# shift_driver.net
KiCad netlist of a schematic drawn in EAGLE
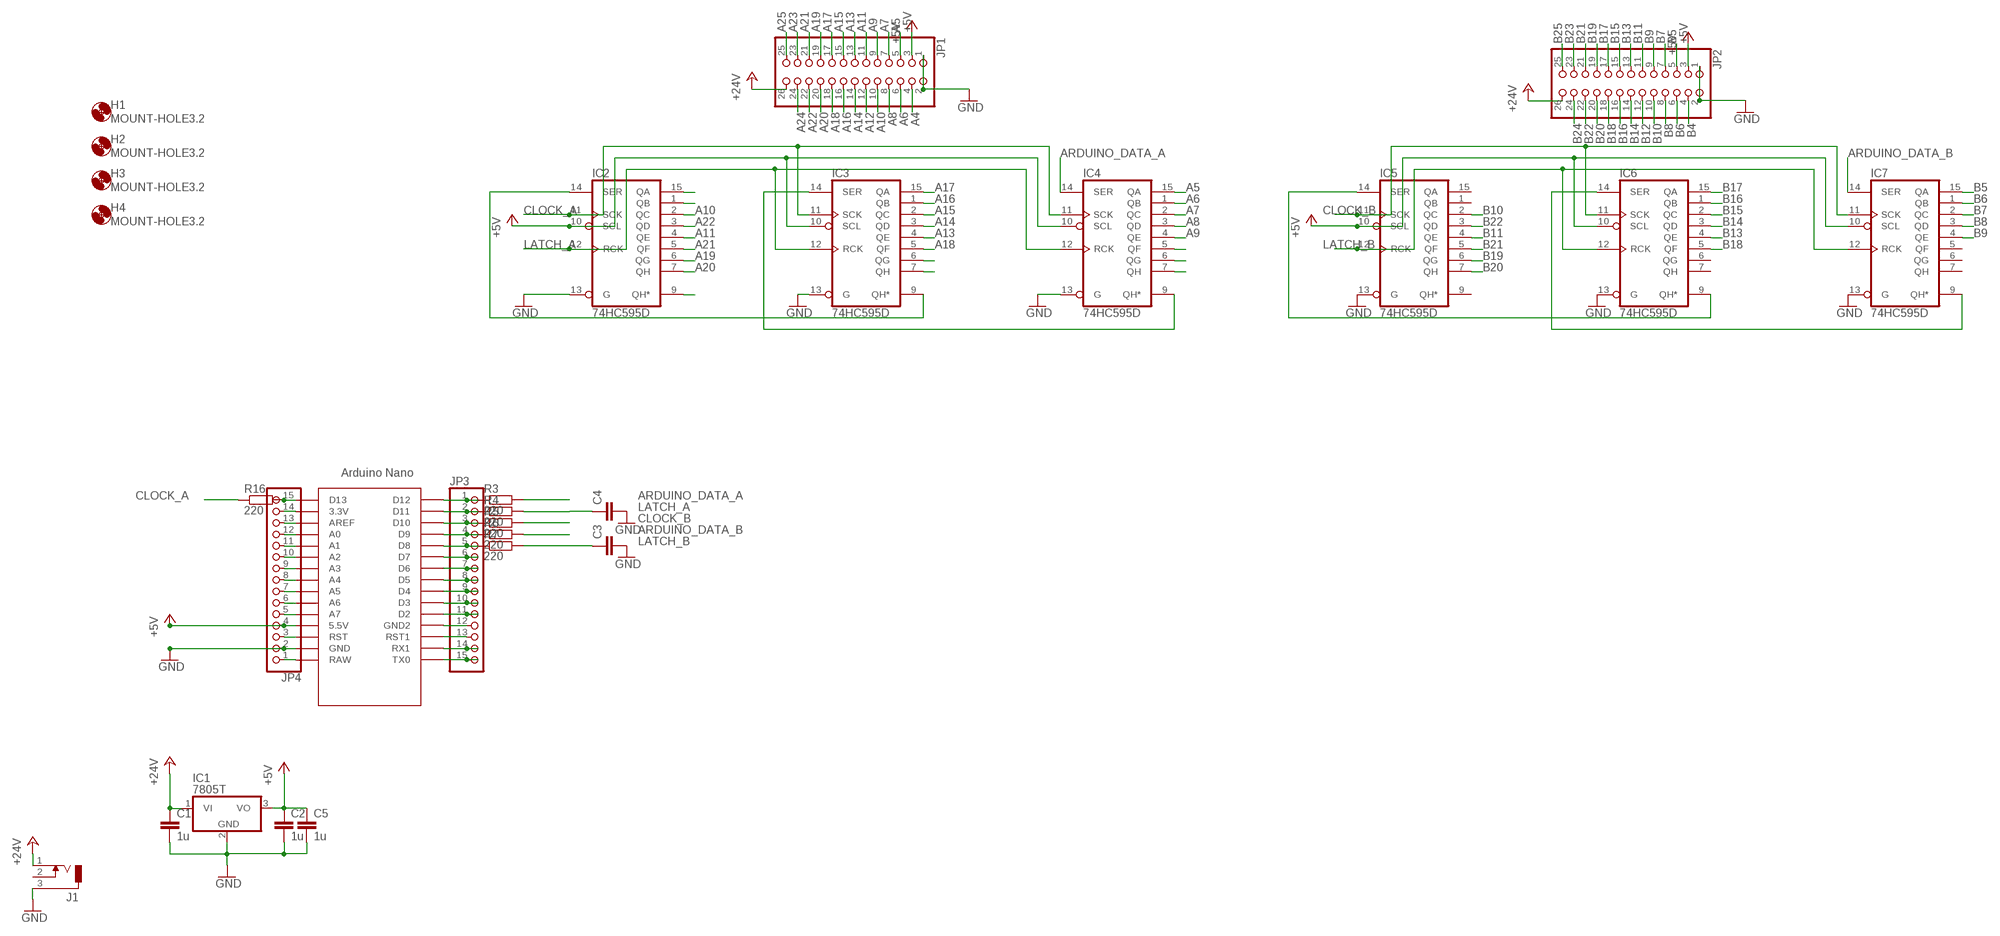
[diagram p0: schematic, sheet 1]

(export (version "E")
  (design (tool "Eeschema 10.0.6"))
  (components
    (comp (ref "C1")
      (value "1u")
      (footprint "eagle-import:C0805")
      (libsource (lib "eagle-import") (part "C-EUC0805"))
    )
    (comp (ref "C2")
      (value "1u")
      (footprint "eagle-import:C0805")
      (libsource (lib "eagle-import") (part "C-EUC0805"))
    )
    (comp (ref "C3")
      (value "C-EUC0805")
      (footprint "eagle-import:C0805")
      (libsource (lib "eagle-import") (part "C-EUC0805"))
    )
    (comp (ref "C4")
      (value "C-EUC0805")
      (footprint "eagle-import:C0805")
      (libsource (lib "eagle-import") (part "C-EUC0805"))
    )
    (comp (ref "C5")
      (value "1u")
      (footprint "eagle-import:C0805")
      (libsource (lib "eagle-import") (part "C-EUC0805"))
    )
    (comp (ref "H1")
      (value "MOUNT-HOLE3.2")
      (footprint "eagle-import:3,2")
      (libsource (lib "eagle-import") (part "MOUNT-HOLE3.2"))
    )
    (comp (ref "H2")
      (value "MOUNT-HOLE3.2")
      (footprint "eagle-import:3,2")
      (libsource (lib "eagle-import") (part "MOUNT-HOLE3.2"))
    )
    (comp (ref "H3")
      (value "MOUNT-HOLE3.2")
      (footprint "eagle-import:3,2")
      (libsource (lib "eagle-import") (part "MOUNT-HOLE3.2"))
    )
    (comp (ref "H4")
      (value "MOUNT-HOLE3.2")
      (footprint "eagle-import:3,2")
      (libsource (lib "eagle-import") (part "MOUNT-HOLE3.2"))
    )
    (comp (ref "IC1")
      (value "7805T")
      (footprint "eagle-import:TO220H")
      (libsource (lib "eagle-import") (part "78T05"))
    )
    (comp (ref "IC2")
      (value "74HC595D")
      (footprint "eagle-import:SO16")
      (libsource (lib "eagle-import") (part "74595DHC"))
    )
    (comp (ref "IC3")
      (value "74HC595D")
      (footprint "eagle-import:SO16")
      (libsource (lib "eagle-import") (part "74595DHC"))
    )
    (comp (ref "IC4")
      (value "74HC595D")
      (footprint "eagle-import:SO16")
      (libsource (lib "eagle-import") (part "74595DHC"))
    )
    (comp (ref "IC5")
      (value "74HC595D")
      (footprint "eagle-import:SO16")
      (libsource (lib "eagle-import") (part "74595DHC"))
    )
    (comp (ref "IC6")
      (value "74HC595D")
      (footprint "eagle-import:SO16")
      (libsource (lib "eagle-import") (part "74595DHC"))
    )
    (comp (ref "IC7")
      (value "74HC595D")
      (footprint "eagle-import:SO16")
      (libsource (lib "eagle-import") (part "74595DHC"))
    )
    (comp (ref "J1")
      (value "DCJ0303")
      (footprint "eagle-import:DCJ0303")
      (libsource (lib "eagle-import") (part "DCJ0303"))
    )
    (comp (ref "JP1")
      (value "PINHD-2X13")
      (footprint "eagle-import:2X13")
      (libsource (lib "eagle-import") (part "PINHD-2X13"))
    )
    (comp (ref "JP2")
      (value "PINHD-2X13")
      (footprint "eagle-import:2X13")
      (libsource (lib "eagle-import") (part "PINHD-2X13"))
    )
    (comp (ref "JP3")
      (value "PINHD-1X15")
      (footprint "eagle-import:1X15")
      (libsource (lib "eagle-import") (part "PINHD-1X15"))
    )
    (comp (ref "JP4")
      (value "PINHD-1X15")
      (footprint "eagle-import:1X15")
      (libsource (lib "eagle-import") (part "PINHD-1X15"))
    )
    (comp (ref "R3")
      (value "220")
      (footprint "eagle-import:R0603")
      (libsource (lib "eagle-import") (part "R-EU_R0603"))
    )
    (comp (ref "R4")
      (value "220")
      (footprint "eagle-import:R0603")
      (libsource (lib "eagle-import") (part "R-EU_R0603"))
    )
    (comp (ref "R5")
      (value "220")
      (footprint "eagle-import:R0603")
      (libsource (lib "eagle-import") (part "R-EU_R0603"))
    )
    (comp (ref "R6")
      (value "220")
      (footprint "eagle-import:R0603")
      (libsource (lib "eagle-import") (part "R-EU_R0603"))
    )
    (comp (ref "R7")
      (value "220")
      (footprint "eagle-import:R0603")
      (libsource (lib "eagle-import") (part "R-EU_R0603"))
    )
    (comp (ref "R16")
      (value "220")
      (footprint "eagle-import:R0603")
      (libsource (lib "eagle-import") (part "R-EU_R0603"))
    )
    (comp (ref "U$1")
      (value "NANO")
      (footprint "eagle-import:NANO")
      (libsource (lib "eagle-import") (part "NANO"))
    )
  )
  (nets
    (net (code "1") (name "+5V") (class "Default")
      (node (ref "C2") (pin "1") (pinfunction "1_1") (pintype "passive"))
      (node (ref "C5") (pin "1") (pinfunction "1_1") (pintype "passive"))
      (node (ref "IC1") (pin "3") (pinfunction "VO_3") (pintype "passive"))
      (node (ref "IC2") (pin "10") (pinfunction "SCL_10") (pintype "input"))
      (node (ref "IC3") (pin "10") (pinfunction "SCL_10") (pintype "input"))
      (node (ref "IC4") (pin "10") (pinfunction "SCL_10") (pintype "input"))
      (node (ref "IC5") (pin "10") (pinfunction "SCL_10") (pintype "input"))
      (node (ref "IC6") (pin "10") (pinfunction "SCL_10") (pintype "input"))
      (node (ref "IC7") (pin "10") (pinfunction "SCL_10") (pintype "input"))
      (node (ref "JP1") (pin "3") (pinfunction "3_3") (pintype "passive"))
      (node (ref "JP2") (pin "3") (pinfunction "3_3") (pintype "passive"))
      (node (ref "JP4") (pin "4") (pinfunction "4_4") (pintype "passive"))
      (node (ref "U$1") (pin "5V") (pinfunction "5.5V_5V") (pintype "bidirectional"))
    )
    (net (code "2") (name "+24V") (class "Default")
      (node (ref "C1") (pin "1") (pinfunction "1_1") (pintype "passive"))
      (node (ref "IC1") (pin "1") (pinfunction "VI_1") (pintype "input"))
      (node (ref "J1") (pin "1") (pinfunction "1_1") (pintype "passive"))
      (node (ref "JP1") (pin "26") (pinfunction "26_26") (pintype "passive"))
      (node (ref "JP2") (pin "26") (pinfunction "26_26") (pintype "passive"))
    )
    (net (code "3") (name "/A4") (class "Default")
      (node (ref "JP1") (pin "4") (pinfunction "4_4") (pintype "passive"))
    )
    (net (code "4") (name "/A5") (class "Default")
      (node (ref "IC4") (pin "15") (pinfunction "QA_15") (pintype "tri_state"))
      (node (ref "JP1") (pin "5") (pinfunction "5_5") (pintype "passive"))
    )
    (net (code "5") (name "/A6") (class "Default")
      (node (ref "IC4") (pin "1") (pinfunction "QB_1") (pintype "tri_state"))
      (node (ref "JP1") (pin "6") (pinfunction "6_6") (pintype "passive"))
    )
    (net (code "6") (name "/A7") (class "Default")
      (node (ref "IC4") (pin "2") (pinfunction "QC_2") (pintype "tri_state"))
      (node (ref "JP1") (pin "7") (pinfunction "7_7") (pintype "passive"))
    )
    (net (code "7") (name "/A8") (class "Default")
      (node (ref "IC4") (pin "3") (pinfunction "QD_3") (pintype "tri_state"))
      (node (ref "JP1") (pin "8") (pinfunction "8_8") (pintype "passive"))
    )
    (net (code "8") (name "/A9") (class "Default")
      (node (ref "IC4") (pin "4") (pinfunction "QE_4") (pintype "tri_state"))
      (node (ref "JP1") (pin "9") (pinfunction "9_9") (pintype "passive"))
    )
    (net (code "9") (name "/A10") (class "Default")
      (node (ref "IC2") (pin "2") (pinfunction "QC_2") (pintype "tri_state"))
      (node (ref "JP1") (pin "10") (pinfunction "10_10") (pintype "passive"))
    )
    (net (code "10") (name "/A11") (class "Default")
      (node (ref "IC2") (pin "4") (pinfunction "QE_4") (pintype "tri_state"))
      (node (ref "JP1") (pin "11") (pinfunction "11_11") (pintype "passive"))
    )
    (net (code "11") (name "/A12") (class "Default")
      (node (ref "JP1") (pin "12") (pinfunction "12_12") (pintype "passive"))
    )
    (net (code "12") (name "/A13") (class "Default")
      (node (ref "IC3") (pin "4") (pinfunction "QE_4") (pintype "tri_state"))
      (node (ref "JP1") (pin "13") (pinfunction "13_13") (pintype "passive"))
    )
    (net (code "13") (name "/A14") (class "Default")
      (node (ref "IC3") (pin "3") (pinfunction "QD_3") (pintype "tri_state"))
      (node (ref "JP1") (pin "14") (pinfunction "14_14") (pintype "passive"))
    )
    (net (code "14") (name "/A15") (class "Default")
      (node (ref "IC3") (pin "2") (pinfunction "QC_2") (pintype "tri_state"))
      (node (ref "JP1") (pin "15") (pinfunction "15_15") (pintype "passive"))
    )
    (net (code "15") (name "/A16") (class "Default")
      (node (ref "IC3") (pin "1") (pinfunction "QB_1") (pintype "tri_state"))
      (node (ref "JP1") (pin "16") (pinfunction "16_16") (pintype "passive"))
    )
    (net (code "16") (name "/A17") (class "Default")
      (node (ref "IC3") (pin "15") (pinfunction "QA_15") (pintype "tri_state"))
      (node (ref "JP1") (pin "17") (pinfunction "17_17") (pintype "passive"))
    )
    (net (code "17") (name "/A18") (class "Default")
      (node (ref "IC3") (pin "5") (pinfunction "QF_5") (pintype "tri_state"))
      (node (ref "JP1") (pin "18") (pinfunction "18_18") (pintype "passive"))
    )
    (net (code "18") (name "/A19") (class "Default")
      (node (ref "IC2") (pin "6") (pinfunction "QG_6") (pintype "tri_state"))
      (node (ref "JP1") (pin "19") (pinfunction "19_19") (pintype "passive"))
    )
    (net (code "19") (name "/A20") (class "Default")
      (node (ref "IC2") (pin "7") (pinfunction "QH_7") (pintype "tri_state"))
      (node (ref "JP1") (pin "20") (pinfunction "20_20") (pintype "passive"))
    )
    (net (code "20") (name "/A21") (class "Default")
      (node (ref "IC2") (pin "5") (pinfunction "QF_5") (pintype "tri_state"))
      (node (ref "JP1") (pin "21") (pinfunction "21_21") (pintype "passive"))
    )
    (net (code "21") (name "/A22") (class "Default")
      (node (ref "IC2") (pin "3") (pinfunction "QD_3") (pintype "tri_state"))
      (node (ref "JP1") (pin "22") (pinfunction "22_22") (pintype "passive"))
    )
    (net (code "22") (name "/A23") (class "Default")
      (node (ref "JP1") (pin "23") (pinfunction "23_23") (pintype "passive"))
    )
    (net (code "23") (name "/A24") (class "Default")
      (node (ref "JP1") (pin "24") (pinfunction "24_24") (pintype "passive"))
    )
    (net (code "24") (name "/A25") (class "Default")
      (node (ref "JP1") (pin "25") (pinfunction "25_25") (pintype "passive"))
    )
    (net (code "25") (name "/ARDUINO_DATA_A") (class "Default")
      (node (ref "IC4") (pin "14") (pinfunction "SER_14") (pintype "input"))
      (node (ref "R3") (pin "2") (pinfunction "2_2") (pintype "passive"))
    )
    (net (code "26") (name "/ARDUINO_DATA_B") (class "Default")
      (node (ref "IC7") (pin "14") (pinfunction "SER_14") (pintype "input"))
      (node (ref "R6") (pin "2") (pinfunction "2_2") (pintype "passive"))
    )
    (net (code "27") (name "/B4") (class "Default")
      (node (ref "JP2") (pin "4") (pinfunction "4_4") (pintype "passive"))
    )
    (net (code "28") (name "/B5") (class "Default")
      (node (ref "IC7") (pin "15") (pinfunction "QA_15") (pintype "tri_state"))
      (node (ref "JP2") (pin "5") (pinfunction "5_5") (pintype "passive"))
    )
    (net (code "29") (name "/B6") (class "Default")
      (node (ref "IC7") (pin "1") (pinfunction "QB_1") (pintype "tri_state"))
      (node (ref "JP2") (pin "6") (pinfunction "6_6") (pintype "passive"))
    )
    (net (code "30") (name "/B7") (class "Default")
      (node (ref "IC7") (pin "2") (pinfunction "QC_2") (pintype "tri_state"))
      (node (ref "JP2") (pin "7") (pinfunction "7_7") (pintype "passive"))
    )
    (net (code "31") (name "/B8") (class "Default")
      (node (ref "IC7") (pin "3") (pinfunction "QD_3") (pintype "tri_state"))
      (node (ref "JP2") (pin "8") (pinfunction "8_8") (pintype "passive"))
    )
    (net (code "32") (name "/B9") (class "Default")
      (node (ref "IC7") (pin "4") (pinfunction "QE_4") (pintype "tri_state"))
      (node (ref "JP2") (pin "9") (pinfunction "9_9") (pintype "passive"))
    )
    (net (code "33") (name "/B10") (class "Default")
      (node (ref "IC5") (pin "2") (pinfunction "QC_2") (pintype "tri_state"))
      (node (ref "JP2") (pin "10") (pinfunction "10_10") (pintype "passive"))
    )
    (net (code "34") (name "/B11") (class "Default")
      (node (ref "IC5") (pin "4") (pinfunction "QE_4") (pintype "tri_state"))
      (node (ref "JP2") (pin "11") (pinfunction "11_11") (pintype "passive"))
    )
    (net (code "35") (name "/B12") (class "Default")
      (node (ref "JP2") (pin "12") (pinfunction "12_12") (pintype "passive"))
    )
    (net (code "36") (name "/B13") (class "Default")
      (node (ref "IC6") (pin "4") (pinfunction "QE_4") (pintype "tri_state"))
      (node (ref "JP2") (pin "13") (pinfunction "13_13") (pintype "passive"))
    )
    (net (code "37") (name "/B14") (class "Default")
      (node (ref "IC6") (pin "3") (pinfunction "QD_3") (pintype "tri_state"))
      (node (ref "JP2") (pin "14") (pinfunction "14_14") (pintype "passive"))
    )
    (net (code "38") (name "/B15") (class "Default")
      (node (ref "IC6") (pin "2") (pinfunction "QC_2") (pintype "tri_state"))
      (node (ref "JP2") (pin "15") (pinfunction "15_15") (pintype "passive"))
    )
    (net (code "39") (name "/B16") (class "Default")
      (node (ref "IC6") (pin "1") (pinfunction "QB_1") (pintype "tri_state"))
      (node (ref "JP2") (pin "16") (pinfunction "16_16") (pintype "passive"))
    )
    (net (code "40") (name "/B17") (class "Default")
      (node (ref "IC6") (pin "15") (pinfunction "QA_15") (pintype "tri_state"))
      (node (ref "JP2") (pin "17") (pinfunction "17_17") (pintype "passive"))
    )
    (net (code "41") (name "/B18") (class "Default")
      (node (ref "IC6") (pin "5") (pinfunction "QF_5") (pintype "tri_state"))
      (node (ref "JP2") (pin "18") (pinfunction "18_18") (pintype "passive"))
    )
    (net (code "42") (name "/B19") (class "Default")
      (node (ref "IC5") (pin "6") (pinfunction "QG_6") (pintype "tri_state"))
      (node (ref "JP2") (pin "19") (pinfunction "19_19") (pintype "passive"))
    )
    (net (code "43") (name "/B20") (class "Default")
      (node (ref "IC5") (pin "7") (pinfunction "QH_7") (pintype "tri_state"))
      (node (ref "JP2") (pin "20") (pinfunction "20_20") (pintype "passive"))
    )
    (net (code "44") (name "/B21") (class "Default")
      (node (ref "IC5") (pin "5") (pinfunction "QF_5") (pintype "tri_state"))
      (node (ref "JP2") (pin "21") (pinfunction "21_21") (pintype "passive"))
    )
    (net (code "45") (name "/B22") (class "Default")
      (node (ref "IC5") (pin "3") (pinfunction "QD_3") (pintype "tri_state"))
      (node (ref "JP2") (pin "22") (pinfunction "22_22") (pintype "passive"))
    )
    (net (code "46") (name "/B23") (class "Default")
      (node (ref "JP2") (pin "23") (pinfunction "23_23") (pintype "passive"))
    )
    (net (code "47") (name "/B24") (class "Default")
      (node (ref "JP2") (pin "24") (pinfunction "24_24") (pintype "passive"))
    )
    (net (code "48") (name "/B25") (class "Default")
      (node (ref "JP2") (pin "25") (pinfunction "25_25") (pintype "passive"))
    )
    (net (code "49") (name "/CLOCK_A") (class "Default")
      (node (ref "IC2") (pin "11") (pinfunction "SCK_11") (pintype "input"))
      (node (ref "IC3") (pin "11") (pinfunction "SCK_11") (pintype "input"))
      (node (ref "IC4") (pin "11") (pinfunction "SCK_11") (pintype "input"))
      (node (ref "R16") (pin "1") (pinfunction "1_1") (pintype "passive"))
    )
    (net (code "50") (name "/CLOCK_B") (class "Default")
      (node (ref "IC5") (pin "11") (pinfunction "SCK_11") (pintype "input"))
      (node (ref "IC6") (pin "11") (pinfunction "SCK_11") (pintype "input"))
      (node (ref "IC7") (pin "11") (pinfunction "SCK_11") (pintype "input"))
      (node (ref "R5") (pin "2") (pinfunction "2_2") (pintype "passive"))
    )
    (net (code "51") (name "/LATCH_A") (class "Default")
      (node (ref "C4") (pin "1") (pinfunction "1_1") (pintype "passive"))
      (node (ref "IC2") (pin "12") (pinfunction "RCK_12") (pintype "input"))
      (node (ref "IC3") (pin "12") (pinfunction "RCK_12") (pintype "input"))
      (node (ref "IC4") (pin "12") (pinfunction "RCK_12") (pintype "input"))
      (node (ref "R4") (pin "2") (pinfunction "2_2") (pintype "passive"))
    )
    (net (code "52") (name "/LATCH_B") (class "Default")
      (node (ref "C3") (pin "1") (pinfunction "1_1") (pintype "passive"))
      (node (ref "IC5") (pin "12") (pinfunction "RCK_12") (pintype "input"))
      (node (ref "IC6") (pin "12") (pinfunction "RCK_12") (pintype "input"))
      (node (ref "IC7") (pin "12") (pinfunction "RCK_12") (pintype "input"))
      (node (ref "R7") (pin "2") (pinfunction "2_2") (pintype "passive"))
    )
    (net (code "53") (name "GND") (class "Default")
      (node (ref "C1") (pin "2") (pinfunction "2_2") (pintype "passive"))
      (node (ref "C2") (pin "2") (pinfunction "2_2") (pintype "passive"))
      (node (ref "C3") (pin "2") (pinfunction "2_2") (pintype "passive"))
      (node (ref "C4") (pin "2") (pinfunction "2_2") (pintype "passive"))
      (node (ref "C5") (pin "2") (pinfunction "2_2") (pintype "passive"))
      (node (ref "IC1") (pin "2") (pinfunction "GND_2") (pintype "passive"))
      (node (ref "IC2") (pin "13") (pinfunction "G_13") (pintype "input"))
      (node (ref "IC3") (pin "13") (pinfunction "G_13") (pintype "input"))
      (node (ref "IC4") (pin "13") (pinfunction "G_13") (pintype "input"))
      (node (ref "IC5") (pin "13") (pinfunction "G_13") (pintype "input"))
      (node (ref "IC6") (pin "13") (pinfunction "G_13") (pintype "input"))
      (node (ref "IC7") (pin "13") (pinfunction "G_13") (pintype "input"))
      (node (ref "J1") (pin "3") (pinfunction "3_3") (pintype "passive"))
      (node (ref "JP1") (pin "1") (pinfunction "1_1") (pintype "passive"))
      (node (ref "JP1") (pin "2") (pinfunction "2_2") (pintype "passive"))
      (node (ref "JP2") (pin "1") (pinfunction "1_1") (pintype "passive"))
      (node (ref "JP2") (pin "2") (pinfunction "2_2") (pintype "passive"))
      (node (ref "JP4") (pin "2") (pinfunction "2_2") (pintype "passive"))
      (node (ref "U$1") (pin "GND") (pinfunction "GND_GND") (pintype "bidirectional"))
    )
    (net (code "54") (name "Net-(IC2A-SER)") (class "Default")
      (node (ref "IC2") (pin "14") (pinfunction "SER_14") (pintype "input"))
      (node (ref "IC3") (pin "9") (pinfunction "QH*_9") (pintype "tri_state"))
    )
    (net (code "55") (name "Net-(IC3A-SER)") (class "Default")
      (node (ref "IC3") (pin "14") (pinfunction "SER_14") (pintype "input"))
      (node (ref "IC4") (pin "9") (pinfunction "QH*_9") (pintype "tri_state"))
    )
    (net (code "56") (name "Net-(IC5A-SER)") (class "Default")
      (node (ref "IC5") (pin "14") (pinfunction "SER_14") (pintype "input"))
      (node (ref "IC6") (pin "9") (pinfunction "QH*_9") (pintype "tri_state"))
    )
    (net (code "57") (name "Net-(IC6A-SER)") (class "Default")
      (node (ref "IC6") (pin "14") (pinfunction "SER_14") (pintype "input"))
      (node (ref "IC7") (pin "9") (pinfunction "QH*_9") (pintype "tri_state"))
    )
    (net (code "58") (name "Net-(JP3-Pad1)") (class "Default")
      (node (ref "JP3") (pin "1") (pinfunction "1_1") (pintype "passive"))
      (node (ref "R3") (pin "1") (pinfunction "1_1") (pintype "passive"))
      (node (ref "U$1") (pin "D12") (pinfunction "D12_D12") (pintype "bidirectional"))
    )
    (net (code "59") (name "Net-(JP3-Pad2)") (class "Default")
      (node (ref "JP3") (pin "2") (pinfunction "2_2") (pintype "passive"))
      (node (ref "R4") (pin "1") (pinfunction "1_1") (pintype "passive"))
      (node (ref "U$1") (pin "D11") (pinfunction "D11_D11") (pintype "bidirectional"))
    )
    (net (code "60") (name "Net-(JP3-Pad3)") (class "Default")
      (node (ref "JP3") (pin "3") (pinfunction "3_3") (pintype "passive"))
      (node (ref "R5") (pin "1") (pinfunction "1_1") (pintype "passive"))
      (node (ref "U$1") (pin "D10") (pinfunction "D10_D10") (pintype "bidirectional"))
    )
    (net (code "61") (name "Net-(JP3-Pad4)") (class "Default")
      (node (ref "JP3") (pin "4") (pinfunction "4_4") (pintype "passive"))
      (node (ref "R6") (pin "1") (pinfunction "1_1") (pintype "passive"))
      (node (ref "U$1") (pin "D9") (pinfunction "D9_D9") (pintype "bidirectional"))
    )
    (net (code "62") (name "Net-(JP3-Pad5)") (class "Default")
      (node (ref "JP3") (pin "5") (pinfunction "5_5") (pintype "passive"))
      (node (ref "R7") (pin "1") (pinfunction "1_1") (pintype "passive"))
      (node (ref "U$1") (pin "D8") (pinfunction "D8_D8") (pintype "bidirectional"))
    )
    (net (code "63") (name "Net-(JP3-Pad6)") (class "Default")
      (node (ref "JP3") (pin "6") (pinfunction "6_6") (pintype "passive"))
      (node (ref "U$1") (pin "D7") (pinfunction "D7_D7") (pintype "bidirectional"))
    )
    (net (code "64") (name "Net-(JP3-Pad7)") (class "Default")
      (node (ref "JP3") (pin "7") (pinfunction "7_7") (pintype "passive"))
      (node (ref "U$1") (pin "D6") (pinfunction "D6_D6") (pintype "bidirectional"))
    )
    (net (code "65") (name "Net-(JP3-Pad8)") (class "Default")
      (node (ref "JP3") (pin "8") (pinfunction "8_8") (pintype "passive"))
      (node (ref "U$1") (pin "D5") (pinfunction "D5_D5") (pintype "bidirectional"))
    )
    (net (code "66") (name "Net-(JP3-Pad9)") (class "Default")
      (node (ref "JP3") (pin "9") (pinfunction "9_9") (pintype "passive"))
      (node (ref "U$1") (pin "D4") (pinfunction "D4_D4") (pintype "bidirectional"))
    )
    (net (code "67") (name "Net-(JP3-Pad10)") (class "Default")
      (node (ref "JP3") (pin "10") (pinfunction "10_10") (pintype "passive"))
      (node (ref "U$1") (pin "D3") (pinfunction "D3_D3") (pintype "bidirectional"))
    )
    (net (code "68") (name "Net-(JP3-Pad11)") (class "Default")
      (node (ref "JP3") (pin "11") (pinfunction "11_11") (pintype "passive"))
      (node (ref "U$1") (pin "D2") (pinfunction "D2_D2") (pintype "bidirectional"))
    )
    (net (code "69") (name "Net-(JP3-Pad13)") (class "Default")
      (node (ref "JP3") (pin "13") (pinfunction "13_13") (pintype "passive"))
      (node (ref "U$1") (pin "RST1") (pinfunction "RST1_RST1") (pintype "bidirectional"))
    )
    (net (code "70") (name "Net-(JP3-Pad14)") (class "Default")
      (node (ref "JP3") (pin "14") (pinfunction "14_14") (pintype "passive"))
      (node (ref "U$1") (pin "RX1") (pinfunction "RX1_RX1") (pintype "bidirectional"))
    )
    (net (code "71") (name "Net-(JP3-Pad15)") (class "Default")
      (node (ref "JP3") (pin "15") (pinfunction "15_15") (pintype "passive"))
      (node (ref "U$1") (pin "TX0") (pinfunction "TX0_TX0") (pintype "bidirectional"))
    )
    (net (code "72") (name "Net-(JP4-Pad1)") (class "Default")
      (node (ref "JP4") (pin "1") (pinfunction "1_1") (pintype "passive"))
      (node (ref "U$1") (pin "RAW") (pinfunction "RAW_RAW") (pintype "bidirectional"))
    )
    (net (code "73") (name "Net-(JP4-Pad3)") (class "Default")
      (node (ref "JP4") (pin "3") (pinfunction "3_3") (pintype "passive"))
      (node (ref "U$1") (pin "RST") (pinfunction "RST_RST") (pintype "bidirectional"))
    )
    (net (code "74") (name "Net-(JP4-Pad5)") (class "Default")
      (node (ref "JP4") (pin "5") (pinfunction "5_5") (pintype "passive"))
      (node (ref "U$1") (pin "A7") (pinfunction "A7_A7") (pintype "bidirectional"))
    )
    (net (code "75") (name "Net-(JP4-Pad6)") (class "Default")
      (node (ref "JP4") (pin "6") (pinfunction "6_6") (pintype "passive"))
      (node (ref "U$1") (pin "A6") (pinfunction "A6_A6") (pintype "bidirectional"))
    )
    (net (code "76") (name "Net-(JP4-Pad7)") (class "Default")
      (node (ref "JP4") (pin "7") (pinfunction "7_7") (pintype "passive"))
      (node (ref "U$1") (pin "A5") (pinfunction "A5_A5") (pintype "bidirectional"))
    )
    (net (code "77") (name "Net-(JP4-Pad8)") (class "Default")
      (node (ref "JP4") (pin "8") (pinfunction "8_8") (pintype "passive"))
      (node (ref "U$1") (pin "A4") (pinfunction "A4_A4") (pintype "bidirectional"))
    )
    (net (code "78") (name "Net-(JP4-Pad9)") (class "Default")
      (node (ref "JP4") (pin "9") (pinfunction "9_9") (pintype "passive"))
      (node (ref "U$1") (pin "A3") (pinfunction "A3_A3") (pintype "bidirectional"))
    )
    (net (code "79") (name "Net-(JP4-Pad10)") (class "Default")
      (node (ref "JP4") (pin "10") (pinfunction "10_10") (pintype "passive"))
      (node (ref "U$1") (pin "A2") (pinfunction "A2_A2") (pintype "bidirectional"))
    )
    (net (code "80") (name "Net-(JP4-Pad11)") (class "Default")
      (node (ref "JP4") (pin "11") (pinfunction "11_11") (pintype "passive"))
      (node (ref "U$1") (pin "A1") (pinfunction "A1_A1") (pintype "bidirectional"))
    )
    (net (code "81") (name "Net-(JP4-Pad12)") (class "Default")
      (node (ref "JP4") (pin "12") (pinfunction "12_12") (pintype "passive"))
      (node (ref "U$1") (pin "A0") (pinfunction "A0_A0") (pintype "bidirectional"))
    )
    (net (code "82") (name "Net-(JP4-Pad13)") (class "Default")
      (node (ref "JP4") (pin "13") (pinfunction "13_13") (pintype "passive"))
      (node (ref "U$1") (pin "AREF") (pinfunction "AREF_AREF") (pintype "bidirectional"))
    )
    (net (code "83") (name "Net-(JP4-Pad14)") (class "Default")
      (node (ref "JP4") (pin "14") (pinfunction "14_14") (pintype "passive"))
      (node (ref "U$1") (pin "3.3V") (pinfunction "3.3V_3.3V") (pintype "bidirectional"))
    )
    (net (code "84") (name "Net-(JP4-Pad15)") (class "Default")
      (node (ref "JP4") (pin "15") (pinfunction "15_15") (pintype "passive"))
      (node (ref "R16") (pin "2") (pinfunction "2_2") (pintype "passive"))
      (node (ref "U$1") (pin "D13") (pinfunction "D13_D13") (pintype "bidirectional"))
    )
    (net (code "85") (name "Net-(U$1-GND2)") (class "Default")
      (node (ref "JP3") (pin "12") (pinfunction "12_12") (pintype "passive"))
      (node (ref "U$1") (pin "GND1") (pinfunction "GND2_GND1") (pintype "bidirectional"))
    )
    (net (code "86") (name "unconnected-(IC2A-QA-Pad15)") (class "Default")
      (node (ref "IC2") (pin "15") (pinfunction "QA_15") (pintype "tri_state"))
    )
    (net (code "87") (name "unconnected-(IC2A-QB-Pad1)") (class "Default")
      (node (ref "IC2") (pin "1") (pinfunction "QB_1") (pintype "tri_state"))
    )
    (net (code "88") (name "unconnected-(IC2A-QH*-Pad9)") (class "Default")
      (node (ref "IC2") (pin "9") (pinfunction "QH*_9") (pintype "tri_state"))
    )
    (net (code "89") (name "unconnected-(IC3A-QG-Pad6)") (class "Default")
      (node (ref "IC3") (pin "6") (pinfunction "QG_6") (pintype "tri_state"))
    )
    (net (code "90") (name "unconnected-(IC3A-QH-Pad7)") (class "Default")
      (node (ref "IC3") (pin "7") (pinfunction "QH_7") (pintype "tri_state"))
    )
    (net (code "91") (name "unconnected-(IC4A-QF-Pad5)") (class "Default")
      (node (ref "IC4") (pin "5") (pinfunction "QF_5") (pintype "tri_state"))
    )
    (net (code "92") (name "unconnected-(IC4A-QG-Pad6)") (class "Default")
      (node (ref "IC4") (pin "6") (pinfunction "QG_6") (pintype "tri_state"))
    )
    (net (code "93") (name "unconnected-(IC4A-QH-Pad7)") (class "Default")
      (node (ref "IC4") (pin "7") (pinfunction "QH_7") (pintype "tri_state"))
    )
    (net (code "94") (name "unconnected-(IC5A-QA-Pad15)") (class "Default")
      (node (ref "IC5") (pin "15") (pinfunction "QA_15") (pintype "tri_state"))
    )
    (net (code "95") (name "unconnected-(IC5A-QB-Pad1)") (class "Default")
      (node (ref "IC5") (pin "1") (pinfunction "QB_1") (pintype "tri_state"))
    )
    (net (code "96") (name "unconnected-(IC5A-QH*-Pad9)") (class "Default")
      (node (ref "IC5") (pin "9") (pinfunction "QH*_9") (pintype "tri_state"))
    )
    (net (code "97") (name "unconnected-(IC6A-QG-Pad6)") (class "Default")
      (node (ref "IC6") (pin "6") (pinfunction "QG_6") (pintype "tri_state"))
    )
    (net (code "98") (name "unconnected-(IC6A-QH-Pad7)") (class "Default")
      (node (ref "IC6") (pin "7") (pinfunction "QH_7") (pintype "tri_state"))
    )
    (net (code "99") (name "unconnected-(IC7A-QF-Pad5)") (class "Default")
      (node (ref "IC7") (pin "5") (pinfunction "QF_5") (pintype "tri_state"))
    )
    (net (code "100") (name "unconnected-(IC7A-QG-Pad6)") (class "Default")
      (node (ref "IC7") (pin "6") (pinfunction "QG_6") (pintype "tri_state"))
    )
    (net (code "101") (name "unconnected-(IC7A-QH-Pad7)") (class "Default")
      (node (ref "IC7") (pin "7") (pinfunction "QH_7") (pintype "tri_state"))
    )
    (net (code "102") (name "unconnected-(J1-Pad2)") (class "Default")
      (node (ref "J1") (pin "2") (pinfunction "2_2") (pintype "passive"))
    )
    (net (code "103") (name "unconnected-(U$1-PadICSP1)") (class "Default")
      (node (ref "U$1") (pin "ICSP1") (pinfunction "ICSP1_ICSP1") (pintype "bidirectional"))
    )
    (net (code "104") (name "unconnected-(U$1-PadICSP2)") (class "Default")
      (node (ref "U$1") (pin "ICSP2") (pinfunction "ICSP2_ICSP2") (pintype "bidirectional"))
    )
    (net (code "105") (name "unconnected-(U$1-PadICSP3)") (class "Default")
      (node (ref "U$1") (pin "ICSP3") (pinfunction "ICSP3_ICSP3") (pintype "bidirectional"))
    )
    (net (code "106") (name "unconnected-(U$1-PadICSP4)") (class "Default")
      (node (ref "U$1") (pin "ICSP4") (pinfunction "ICSP4_ICSP4") (pintype "bidirectional"))
    )
    (net (code "107") (name "unconnected-(U$1-PadICSP5)") (class "Default")
      (node (ref "U$1") (pin "ICSP5") (pinfunction "ICSP5_ICSP5") (pintype "bidirectional"))
    )
    (net (code "108") (name "unconnected-(U$1-PadICSP6)") (class "Default")
      (node (ref "U$1") (pin "ICSP6") (pinfunction "ICSP6_ICSP6") (pintype "bidirectional"))
    )
  )
)
